# pmic_vicor_brick.net
KiCad netlist of a schematic drawn in Altium Designer
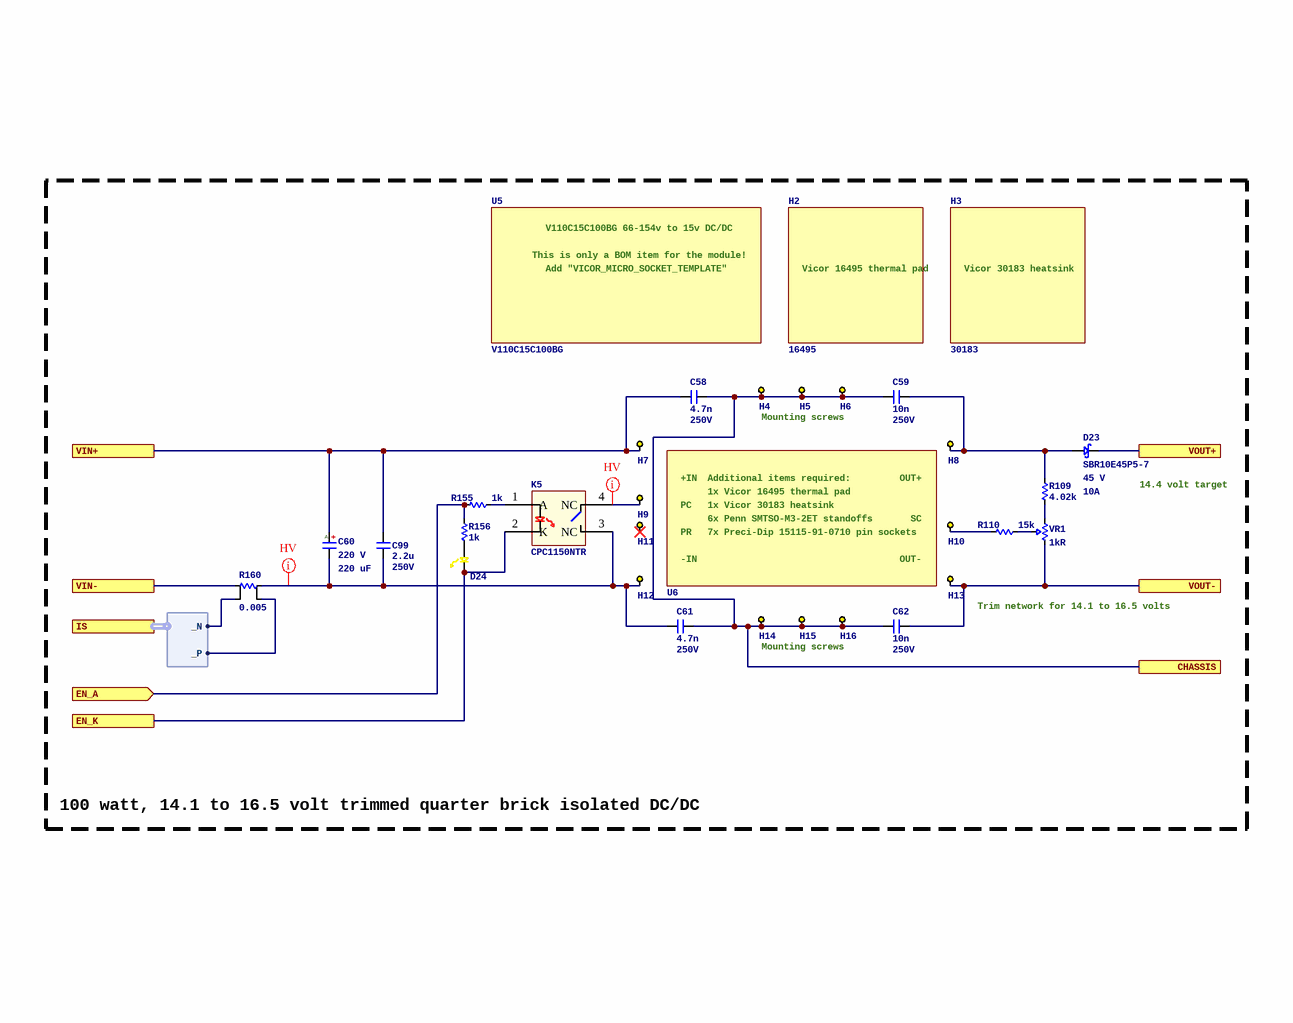
[diagram p0: pmic_vicor_brick.SchDoc]

(export (version "E")
  (design (tool "Eeschema 10.0.6"))
  (components
    (comp (ref "C58")
      (value "GCM21B5C2E472JX01L")
      (footprint "C0805")
      (fields
        (field (name "CAPACITANCE") "4.7n")
        (field (name "MANUFACTURER") "Murata Electronics")
        (field (name "VOLTAGE RATING") "250V")
      )
      (libsource (lib "database") (part "__template_cap"))
    )
    (comp (ref "C59")
      (value "GRM21B5C2E103JWAAL")
      (footprint "C0805")
      (fields
        (field (name "CAPACITANCE") "10n")
        (field (name "MANUFACTURER") "Murata Electronics")
        (field (name "VOLTAGE RATING") "250V")
      )
      (libsource (lib "database") (part "__template_cap"))
    )
    (comp (ref "C60")
      (value "EKXJ221ELL221MM25S")
      (footprint "CAP_1600X2700X750")
      (fields
        (field (name "MANUFACTURER") "United Chemi-Con")
        (field (name "VOLTAGE") "220 V")
        (field (name "CAPACITANCE") "220 uF")
      )
      (libsource (lib "SSCP") (part "AUTO_CAP_ALUM_220UF_220V_EKXJ221ELL221MM25S"))
    )
    (comp (ref "C61")
      (value "GCM21B5C2E472JX01L")
      (footprint "C0805")
      (fields
        (field (name "CAPACITANCE") "4.7n")
        (field (name "MANUFACTURER") "Murata Electronics")
        (field (name "VOLTAGE RATING") "250V")
      )
      (libsource (lib "database") (part "__template_cap"))
    )
    (comp (ref "C62")
      (value "GRM21B5C2E103JWAAL")
      (footprint "C0805")
      (fields
        (field (name "CAPACITANCE") "10n")
        (field (name "MANUFACTURER") "Murata Electronics")
        (field (name "VOLTAGE RATING") "250V")
      )
      (libsource (lib "database") (part "__template_cap"))
    )
    (comp (ref "C99")
      (value "C5750X7T2E225KT000N")
      (footprint "C2220")
      (fields
        (field (name "CAPACITANCE") "2.2u")
        (field (name "MANUFACTURER") "TDK")
        (field (name "VOLTAGE RATING") "250V")
      )
      (libsource (lib "database") (part "__template_cap"))
    )
    (comp (ref "D23")
      (value "SBR10E45P5-7")
      (footprint "POWERDI5")
      (description "Rectifier Diode, 1 Phase, 1 Element, 10A, 45V V(RRM), Silicon")
      (fields
        (field (name "MANUFACTURER") "Diodes")
        (field (name "VOLTAGE") "45 V")
        (field (name "CURRENT") "10A")
      )
      (libsource (lib "SSCP") (part "SCHOTTKY_45V_SBR10E45P5-7"))
    )
    (comp (ref "D24")
      (value "LTST-C190YKT")
      (footprint "LED_0603P_YELLOW")
      (description "LED YELLOW CLEAR 0603 SMD")
      (fields (field (name "MANUFACTURER") "Lite-On Inc"))
      (libsource (lib "SSCP") (part "LED_0603_YELLOW_LTST-C190YKT"))
    )
    (comp (ref "H2")
      (value "16495")
      (description "Heat Sink, Aluminum")
      (fields (field (name "MANUFACTURER") "Vicor") (field (name "MANUFACTURER PART NUMBER") "16495"))
      (libsource (lib "SSCP") (part "VICOR_THERMAL_PAD_16495"))
    )
    (comp (ref "H3")
      (value "30183")
      (footprint "VICOR_HEATSINK_30183")
      (description "Heat Sink, Aluminum")
      (fields (field (name "MANUFACTURER") "Vicor") (field (name "MANUFACTURER PART NUMBER") "30183"))
      (libsource (lib "SSCP") (part "VICOR_HEATSINK_30183"))
    )
    (comp (ref "H4")
      (value "SMTSO-M3-2ET")
      (footprint "SMTSO-M3-2ET")
      (description "Standoff Round Swage F/F M3 X 0.5-THD Carbon Steel Electro-Tin ASTM B545")
      (fields (field (name "MANUFACTURER") "PennEngineering"))
      (libsource (lib "SSCP") (part "STANDOFF_SMTSO-M3-2ET"))
    )
    (comp (ref "H5")
      (value "SMTSO-M3-2ET")
      (footprint "SMTSO-M3-2ET")
      (description "Standoff Round Swage F/F M3 X 0.5-THD Carbon Steel Electro-Tin ASTM B545")
      (fields (field (name "MANUFACTURER") "PennEngineering"))
      (libsource (lib "SSCP") (part "STANDOFF_SMTSO-M3-2ET"))
    )
    (comp (ref "H6")
      (value "SMTSO-M3-2ET")
      (footprint "SMTSO-M3-2ET")
      (description "Standoff Round Swage F/F M3 X 0.5-THD Carbon Steel Electro-Tin ASTM B545")
      (fields (field (name "MANUFACTURER") "PennEngineering"))
      (libsource (lib "SSCP") (part "STANDOFF_SMTSO-M3-2ET"))
    )
    (comp (ref "H7")
      (value "15115-91-0710")
      (footprint "PRECI-DIP_15115-91-0710")
      (description "Pin Receptacle Connector 0.078\" ~ 0.096\" (1.98mm ~ 2.44mm) No Tail Solder")
      (fields (field (name "MANUFACTURER") "Preci-Dip"))
      (libsource (lib "SSCP") (part "PIN_SOCKET_15115-91-0710"))
    )
    (comp (ref "H8")
      (value "15115-91-0710")
      (footprint "PRECI-DIP_15115-91-0710")
      (description "Pin Receptacle Connector 0.078\" ~ 0.096\" (1.98mm ~ 2.44mm) No Tail Solder")
      (fields (field (name "MANUFACTURER") "Preci-Dip"))
      (libsource (lib "SSCP") (part "PIN_SOCKET_15115-91-0710"))
    )
    (comp (ref "H9")
      (value "15115-91-0710")
      (footprint "PRECI-DIP_15115-91-0710")
      (description "Pin Receptacle Connector 0.078\" ~ 0.096\" (1.98mm ~ 2.44mm) No Tail Solder")
      (fields (field (name "MANUFACTURER") "Preci-Dip"))
      (libsource (lib "SSCP") (part "PIN_SOCKET_15115-91-0710"))
    )
    (comp (ref "H10")
      (value "15115-91-0710")
      (footprint "PRECI-DIP_15115-91-0710")
      (description "Pin Receptacle Connector 0.078\" ~ 0.096\" (1.98mm ~ 2.44mm) No Tail Solder")
      (fields (field (name "MANUFACTURER") "Preci-Dip"))
      (libsource (lib "SSCP") (part "PIN_SOCKET_15115-91-0710"))
    )
    (comp (ref "H11")
      (value "15115-91-0710")
      (footprint "PRECI-DIP_15115-91-0710")
      (description "Pin Receptacle Connector 0.078\" ~ 0.096\" (1.98mm ~ 2.44mm) No Tail Solder")
      (fields (field (name "MANUFACTURER") "Preci-Dip"))
      (libsource (lib "SSCP") (part "PIN_SOCKET_15115-91-0710"))
    )
    (comp (ref "H12")
      (value "15115-91-0710")
      (footprint "PRECI-DIP_15115-91-0710")
      (description "Pin Receptacle Connector 0.078\" ~ 0.096\" (1.98mm ~ 2.44mm) No Tail Solder")
      (fields (field (name "MANUFACTURER") "Preci-Dip"))
      (libsource (lib "SSCP") (part "PIN_SOCKET_15115-91-0710"))
    )
    (comp (ref "H13")
      (value "15115-91-0710")
      (footprint "PRECI-DIP_15115-91-0710")
      (description "Pin Receptacle Connector 0.078\" ~ 0.096\" (1.98mm ~ 2.44mm) No Tail Solder")
      (fields (field (name "MANUFACTURER") "Preci-Dip"))
      (libsource (lib "SSCP") (part "PIN_SOCKET_15115-91-0710"))
    )
    (comp (ref "H14")
      (value "SMTSO-M3-2ET")
      (footprint "SMTSO-M3-2ET")
      (description "Standoff Round Swage F/F M3 X 0.5-THD Carbon Steel Electro-Tin ASTM B545")
      (fields (field (name "MANUFACTURER") "PennEngineering"))
      (libsource (lib "SSCP") (part "STANDOFF_SMTSO-M3-2ET"))
    )
    (comp (ref "H15")
      (value "SMTSO-M3-2ET")
      (footprint "SMTSO-M3-2ET")
      (description "Standoff Round Swage F/F M3 X 0.5-THD Carbon Steel Electro-Tin ASTM B545")
      (fields (field (name "MANUFACTURER") "PennEngineering"))
      (libsource (lib "SSCP") (part "STANDOFF_SMTSO-M3-2ET"))
    )
    (comp (ref "H16")
      (value "SMTSO-M3-2ET")
      (footprint "SMTSO-M3-2ET")
      (description "Standoff Round Swage F/F M3 X 0.5-THD Carbon Steel Electro-Tin ASTM B545")
      (fields (field (name "MANUFACTURER") "PennEngineering"))
      (libsource (lib "SSCP") (part "STANDOFF_SMTSO-M3-2ET"))
    )
    (comp (ref "K5")
      (value "CPC1150NTR")
      (footprint "4SMD300")
      (description "CPC1150N Series SPST 120 mA 350 V Single Channel Solid State Relay SMT - SOIC-4")
      (fields (field (name "MANUFACTURER") "Littelfuse"))
      (libsource (lib "SSCP") (part "SSR_350V_CPC1150NTR"))
    )
    (comp (ref "R109")
      (value "4.02k")
      (footprint "R0402")
      (fields
        (field (name "MANUFACTURER PART NUMBER") "0402WGF4021TCE")
        (field (name "MANUFACTURER") "UNI-ROYAL(Uniroyal Elec)")
        (field (name "TOLERANCE") "1%")
      )
      (libsource (lib "database") (part "__template_resistor"))
    )
    (comp (ref "R110")
      (value "15k")
      (footprint "R0402")
      (fields
        (field (name "MANUFACTURER PART NUMBER") "0402WGF1502TCE")
        (field (name "MANUFACTURER") "UNI-ROYAL(Uniroyal Elec)")
        (field (name "TOLERANCE") "1%")
      )
      (libsource (lib "database") (part "__template_resistor"))
    )
    (comp (ref "R155")
      (value "1k")
      (footprint "R0402")
      (fields
        (field (name "TOLERANCE") "1%")
        (field (name "MANUFACTURER PART NUMBER") "0402WGF1001TCE")
        (field (name "MANUFACTURER") "UNI-ROYAL(Uniroyal Elec)")
      )
      (libsource (lib "database") (part "__template_resistor"))
    )
    (comp (ref "R156")
      (value "1k")
      (footprint "R0402")
      (fields
        (field (name "TOLERANCE") "1%")
        (field (name "MANUFACTURER PART NUMBER") "0402WGF1001TCE")
        (field (name "MANUFACTURER") "UNI-ROYAL(Uniroyal Elec)")
      )
      (libsource (lib "database") (part "__template_resistor"))
    )
    (comp (ref "R160")
      (value "WSL27265L000FEB")
      (footprint "VISHAY_WSL2726")
      (description "RES SMD 0.005 OHM 1% 3W 2726")
      (fields (field (name "MANUFACTURER") "Vishay Dale") (field (name "RESISTANCE (OHMS)") "0.005"))
      (libsource (lib "SSCP") (part "RES_CURRENT_SENSE_0.005_OHM_1%_3W_2726_WSL27265L000FEB"))
    )
    (comp (ref "U5")
      (value "V110C15C100BG")
      (description "APSM DCDC, 1 Output, 100W, Hybrid")
      (fields (field (name "MANUFACTURER") "Vicor"))
      (libsource (lib "SSCP") (part "CONV_DCDC_V110C15C100BG_BOM"))
    )
    (comp (ref "U6")
      (value "CONV_DCDC_VICOR_MICRO_SOCKET_TEMPLATE")
      (footprint "VICOR_MICRO_SOCKET_TEMPLATE")
      (description "This is a template for the placement of socket pins and heatsink for a Vicor micro brick")
      (libsource (lib "SSCP") (part "CONV_DCDC_VICOR_MICRO_SOCKET_TEMPLATE"))
    )
    (comp (ref "VR1")
      (value "1kR")
      (footprint "TT_67W")
      (description "Trimmer, Cermet, 0.5W, 20000ohm, 200V, 10% +/-Tol, 100ppm/Cel, 20 Turn(s)")
      (fields (field (name "MANUFACTURER") "TT BI") (field (name "MANUFACTURER PART NUMBER") "67WR1KLF"))
      (libsource (lib "SSCP") (part "POT_1K_OHM_67WR1KLF"))
    )
  )
  (nets
    (net (code "2") (name "/CHASSIS") (class "Default")
      (node (ref "C58") (pin "2") (pintype "passive"))
      (node (ref "C59") (pin "1") (pintype "passive"))
      (node (ref "C61") (pin "2") (pintype "passive"))
      (node (ref "C62") (pin "1") (pintype "passive"))
      (node (ref "H14") (pin "1") (pintype "passive"))
      (node (ref "H15") (pin "1") (pintype "passive"))
      (node (ref "H16") (pin "1") (pintype "passive"))
      (node (ref "H4") (pin "1") (pintype "passive"))
      (node (ref "H5") (pin "1") (pintype "passive"))
      (node (ref "H6") (pin "1") (pintype "passive"))
    )
    (net (code "3") (name "/EN_A") (class "Default")
      (node (ref "R155") (pin "2") (pintype "passive"))
      (node (ref "R156") (pin "1") (pintype "passive"))
    )
    (net (code "4") (name "/EN_K") (class "Default")
      (node (ref "D24") (pin "1") (pintype "passive"))
      (node (ref "K5") (pin "2") (pinfunction "K_2") (pintype "passive"))
    )
    (net (code "5") (name "/VIN+") (class "Default")
      (node (ref "C58") (pin "1") (pintype "passive"))
      (node (ref "C60") (pin "1") (pintype "passive"))
      (node (ref "C99") (pin "1") (pintype "passive"))
      (node (ref "H7") (pin "1") (pintype "passive"))
    )
    (net (code "6") (name "/VIN-") (class "Default") (node (ref "R160") (pin "1") (pintype "passive")))
    (net (code "7") (name "/VOUT+") (class "Default") (node (ref "D23") (pin "2") (pintype "passive")))
    (net (code "8") (name "/VOUT-") (class "Default")
      (node (ref "C62") (pin "2") (pintype "passive"))
      (node (ref "H13") (pin "1") (pintype "passive"))
      (node (ref "VR1") (pin "3") (pintype "passive"))
    )
    (net (code "9") (name "/_N") (class "Default") (node (ref "R160") (pin "3") (pintype "passive")))
    (net (code "10") (name "/_P") (class "Default") (node (ref "R160") (pin "4") (pintype "passive")))
    (net (code "12") (name "Net-(C59-Pad2)") (class "Default")
      (node (ref "C59") (pin "2") (pintype "passive"))
      (node (ref "D23") (pin "1") (pintype "passive"))
      (node (ref "H8") (pin "1") (pintype "passive"))
      (node (ref "R109") (pin "1") (pintype "passive"))
    )
    (net (code "13") (name "Net-(C60-Pad2)") (class "Default")
      (node (ref "C60") (pin "2") (pintype "passive"))
      (node (ref "C61") (pin "1") (pintype "passive"))
      (node (ref "C99") (pin "2") (pintype "passive"))
      (node (ref "H12") (pin "1") (pintype "passive"))
      (node (ref "K5") (pin "3") (pinfunction "NC_3") (pintype "passive"))
      (node (ref "R160") (pin "2") (pintype "passive"))
    )
    (net (code "14") (name "Net-(D24-Pad2)") (class "Default")
      (node (ref "D24") (pin "2") (pintype "passive"))
      (node (ref "R156") (pin "2") (pintype "passive"))
    )
    (net (code "15") (name "Net-(H9-Pad1)") (class "Default")
      (node (ref "H9") (pin "1") (pintype "passive"))
      (node (ref "K5") (pin "4") (pinfunction "NC_4") (pintype "passive"))
    )
    (net (code "16") (name "Net-(H10-Pad1)") (class "Default")
      (node (ref "H10") (pin "1") (pintype "passive"))
      (node (ref "R110") (pin "1") (pintype "passive"))
    )
    (net (code "17") (name "Net-(K5-A)") (class "Default")
      (node (ref "K5") (pin "1") (pinfunction "A_1") (pintype "passive"))
      (node (ref "R155") (pin "1") (pintype "passive"))
    )
    (net (code "18") (name "Net-(R109-Pad2)") (class "Default")
      (node (ref "R109") (pin "2") (pintype "passive"))
      (node (ref "VR1") (pin "1") (pintype "passive"))
    )
    (net (code "19") (name "Net-(R110-Pad2)") (class "Default")
      (node (ref "R110") (pin "2") (pintype "passive"))
      (node (ref "VR1") (pin "2") (pintype "passive"))
    )
    (net (code "20") (name "unconnected-(H11-Pad1)") (class "Default")
      (node (ref "H11") (pin "1") (pintype "passive+no_connect"))
    )
  )
)
